# uController_and_communication.net
KiCad netlist of a schematic drawn in Altium Designer
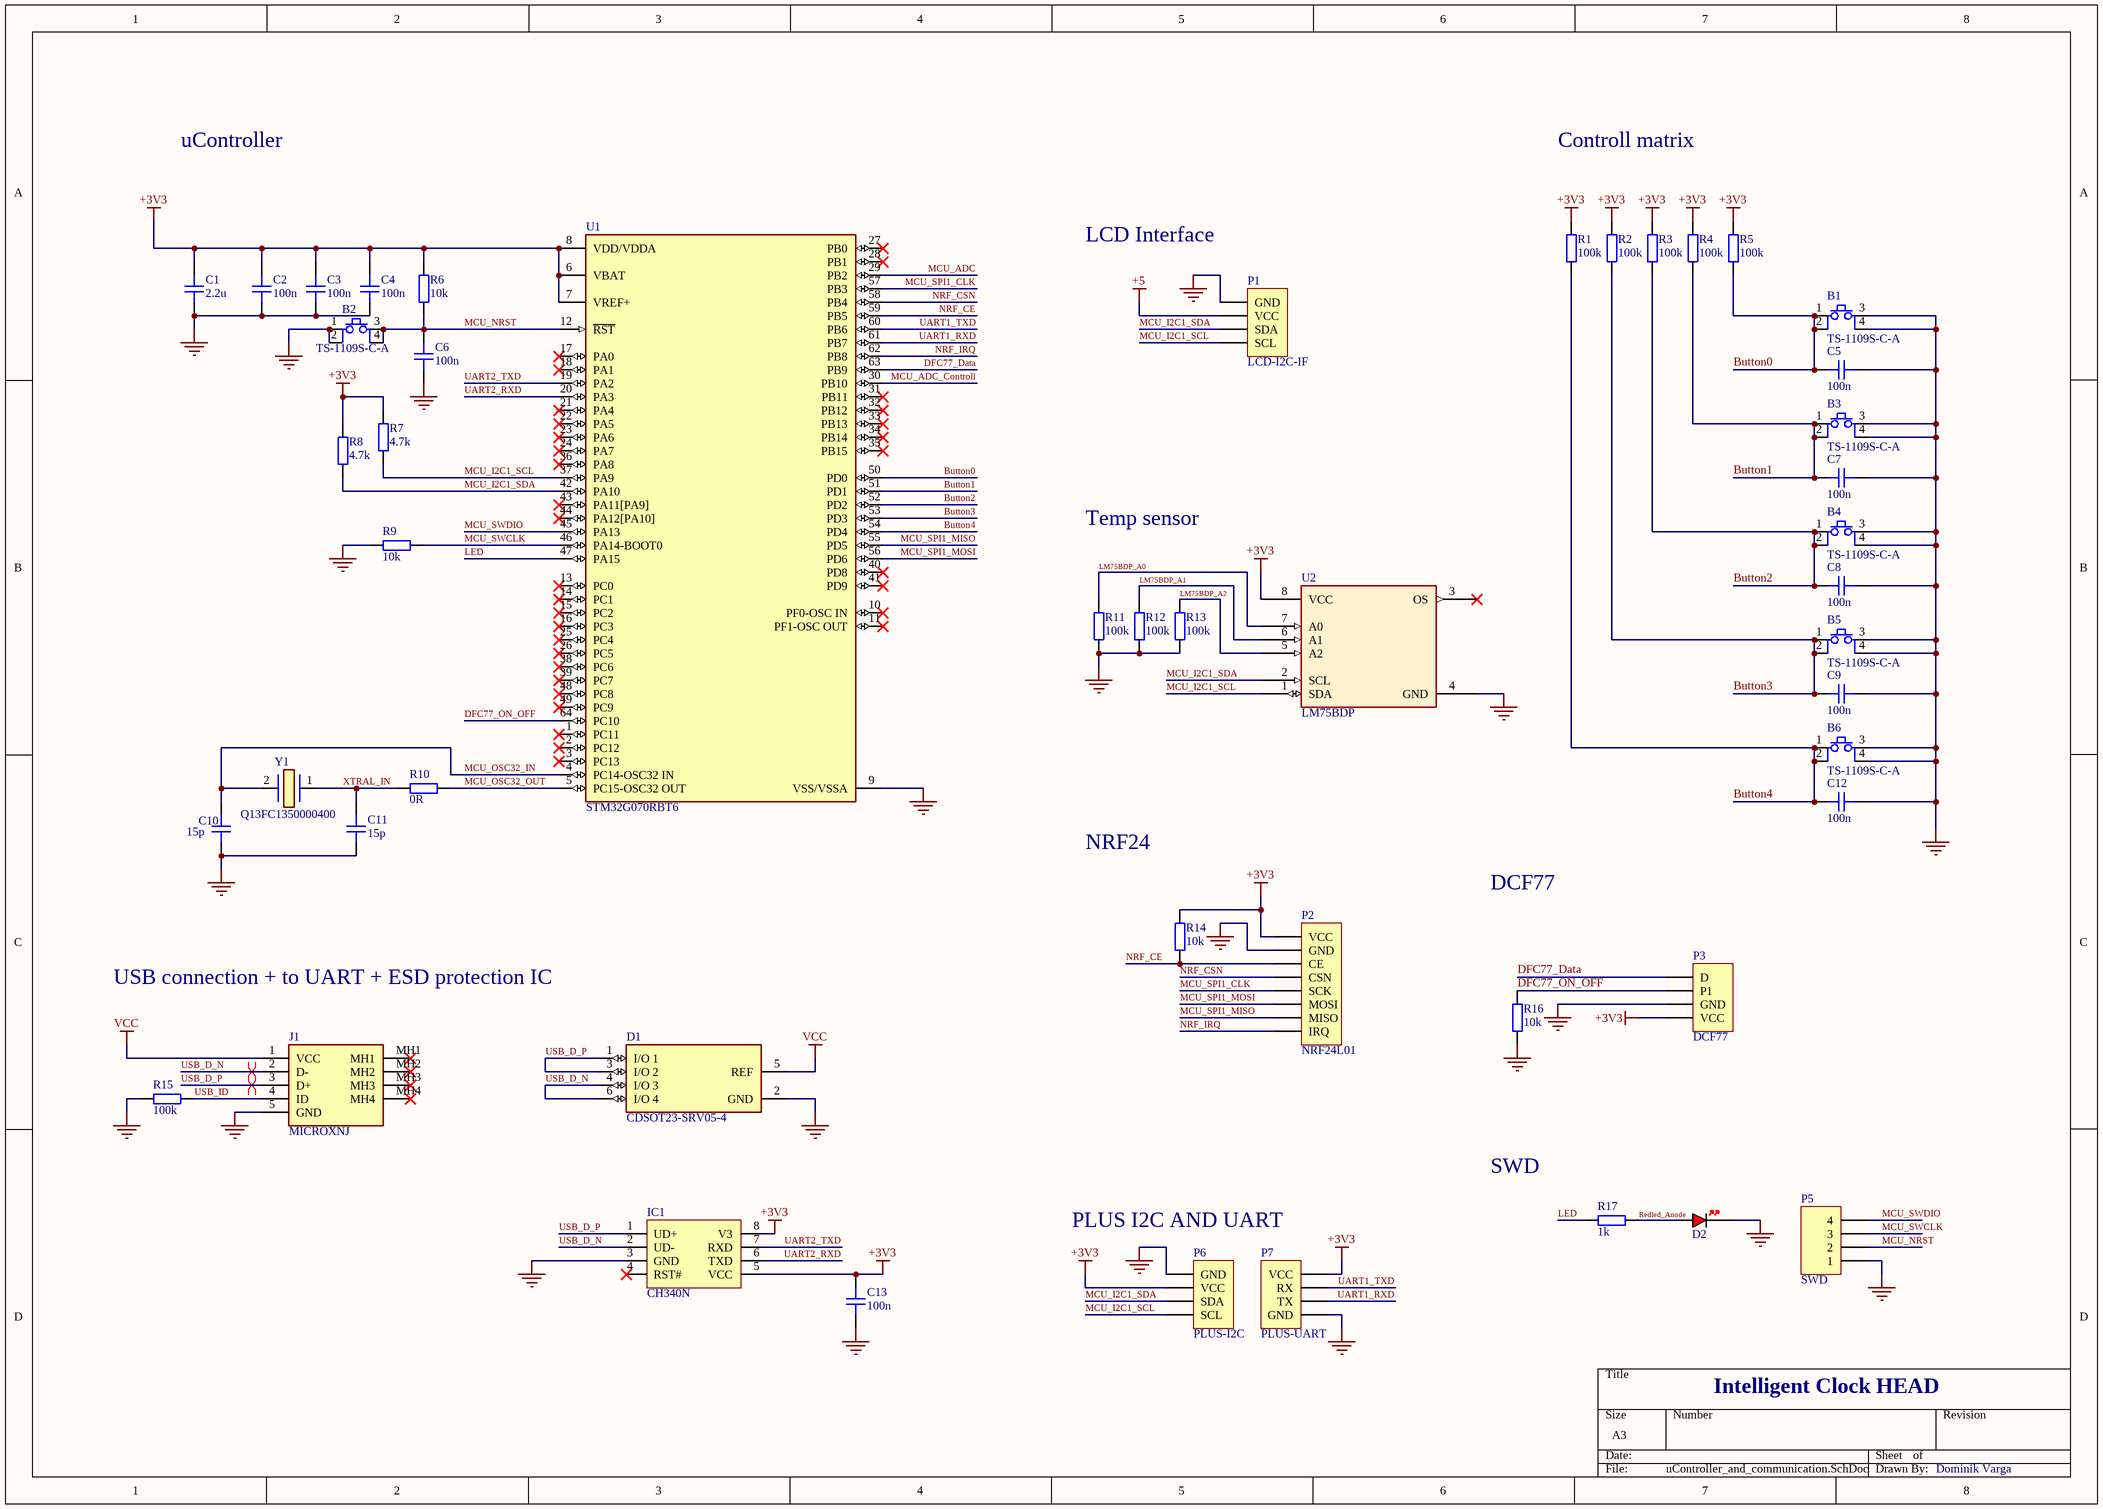
[diagram p0: uController_and_communication.SchDoc]

(export (version "E")
  (design (tool "Eeschema 10.0.6"))
  (components
    (comp (ref "B1")
      (value "TS-1109S-C-A")
      (footprint "SMD_Button")
      (description "Basic SMD button")
      (fields (field (name "MANUFACTURER") "XKB Connectivity"))
      (libsource (lib "OnlabComponents") (part "TS-1109S-C-A"))
    )
    (comp (ref "B2")
      (value "TS-1109S-C-A")
      (footprint "SMD_Button")
      (description "Basic SMD button")
      (fields (field (name "MANUFACTURER") "XKB Connectivity"))
      (libsource (lib "OnlabComponents") (part "TS-1109S-C-A"))
    )
    (comp (ref "B3")
      (value "TS-1109S-C-A")
      (footprint "SMD_Button")
      (description "Basic SMD button")
      (fields (field (name "MANUFACTURER") "XKB Connectivity"))
      (libsource (lib "OnlabComponents") (part "TS-1109S-C-A"))
    )
    (comp (ref "B4")
      (value "TS-1109S-C-A")
      (footprint "SMD_Button")
      (description "Basic SMD button")
      (fields (field (name "MANUFACTURER") "XKB Connectivity"))
      (libsource (lib "OnlabComponents") (part "TS-1109S-C-A"))
    )
    (comp (ref "B5")
      (value "TS-1109S-C-A")
      (footprint "SMD_Button")
      (description "Basic SMD button")
      (fields (field (name "MANUFACTURER") "XKB Connectivity"))
      (libsource (lib "OnlabComponents") (part "TS-1109S-C-A"))
    )
    (comp (ref "B6")
      (value "TS-1109S-C-A")
      (footprint "SMD_Button")
      (description "Basic SMD button")
      (fields (field (name "MANUFACTURER") "XKB Connectivity"))
      (libsource (lib "OnlabComponents") (part "TS-1109S-C-A"))
    )
    (comp (ref "C1")
      (value "2.2u")
      (footprint "CAP_0603")
      (description "Capacitor SMD 0603 10V")
      (libsource (lib "Schematic-Lib-PhilsLab") (part "CAP_0603_10V"))
    )
    (comp (ref "C2")
      (value "100n")
      (footprint "CAP_0603")
      (description "Capacitor SMD 0603 10V")
      (libsource (lib "Schematic-Lib-PhilsLab") (part "CAP_0603_10V"))
    )
    (comp (ref "C3")
      (value "100n")
      (footprint "CAP_0603")
      (description "Capacitor SMD 0603 10V")
      (libsource (lib "Schematic-Lib-PhilsLab") (part "CAP_0603_10V"))
    )
    (comp (ref "C4")
      (value "100n")
      (footprint "CAP_0603")
      (description "Capacitor SMD 0603 10V")
      (libsource (lib "Schematic-Lib-PhilsLab") (part "CAP_0603_10V"))
    )
    (comp (ref "C5")
      (value "100n")
      (footprint "CAP_0603")
      (description "Capacitor SMD 0603 10V")
      (libsource (lib "Schematic-Lib-PhilsLab") (part "CAP_0603_10V"))
    )
    (comp (ref "C6")
      (value "100n")
      (footprint "CAP_0603")
      (description "Capacitor SMD 0603 10V")
      (libsource (lib "Schematic-Lib-PhilsLab") (part "CAP_0603_10V"))
    )
    (comp (ref "C7")
      (value "100n")
      (footprint "CAP_0603")
      (description "Capacitor SMD 0603 10V")
      (libsource (lib "Schematic-Lib-PhilsLab") (part "CAP_0603_10V"))
    )
    (comp (ref "C8")
      (value "100n")
      (footprint "CAP_0603")
      (description "Capacitor SMD 0603 10V")
      (libsource (lib "Schematic-Lib-PhilsLab") (part "CAP_0603_10V"))
    )
    (comp (ref "C9")
      (value "100n")
      (footprint "CAP_0603")
      (description "Capacitor SMD 0603 10V")
      (libsource (lib "Schematic-Lib-PhilsLab") (part "CAP_0603_10V"))
    )
    (comp (ref "C10")
      (value "15p")
      (footprint "CAP_0603")
      (description "Capacitor SMD 0603 10V")
      (libsource (lib "Schematic-Lib-PhilsLab") (part "CAP_0603_10V"))
    )
    (comp (ref "C11")
      (value "15p")
      (footprint "CAP_0603")
      (description "Capacitor SMD 0603 10V")
      (libsource (lib "Schematic-Lib-PhilsLab") (part "CAP_0603_10V"))
    )
    (comp (ref "C12")
      (value "100n")
      (footprint "CAP_0603")
      (description "Capacitor SMD 0603 10V")
      (libsource (lib "Schematic-Lib-PhilsLab") (part "CAP_0603_10V"))
    )
    (comp (ref "C13")
      (value "100n")
      (footprint "CAP_0603")
      (description "Capacitor SMD 0603 10V")
      (libsource (lib "Schematic-Lib-PhilsLab") (part "CAP_0603_10V"))
    )
    (comp (ref "D1")
      (value "CDSOT23-SRV05-4")
      (footprint "FP-CDSOT23-SRV05-4-MFG")
      (description "TVS DIODE 5V 15V SOT23-6")
      (fields
        (field (name "OCTOPART") "https://octopart.com/cdsot23-srv05-4-bourns-1679449")
        (field (name "MANUFACTURER") "Bourns Inc.")
      )
      (libsource (lib "Altium Content Vault") (part "1f9d70c8dcd49be0b2fcd6c5f1da486"))
    )
    (comp (ref "D2")
      (value "RED")
      (footprint "LED_0603_RED")
      (description "LED 0603 RED SMD")
      (libsource (lib "Schematic-Lib-PhilsLab") (part "LED_0603_RED"))
    )
    (comp (ref "IC1")
      (value "CH340N")
      (footprint "SOP127P600X190-8N")
      (description "USB to UART integrated circuit")
      (fields (field (name "MANUFACTURER") "WCH"))
      (libsource (lib "OnlabComponents") (part "CH340N"))
    )
    (comp (ref "J1")
      (value "MICROXNJ")
      (footprint "MICROXNJ")
      (description "Connector")
      (libsource (lib "OnlabComponents") (part "MICROXNJ"))
    )
    (comp (ref "P1")
      (value "LCD-I2C-IF")
      (footprint "HDR1X4")
      (description "Header, 4-Pin")
      (fields (field (name "PUBLISHER") "Altium Limited"))
      (libsource (lib "Miscellaneous Connectors") (part "Header 4"))
    )
    (comp (ref "P2")
      (value "NRF24L01")
      (footprint "MHDR1X8")
      (description "Header, 8-Pin")
      (fields (field (name "PUBLISHER") "Altium Limited"))
      (libsource (lib "Miscellaneous Connectors") (part "MHDR1X8"))
    )
    (comp (ref "P3")
      (value "DCF77")
      (footprint "HDR1X4")
      (description "Header, 4-Pin")
      (fields (field (name "PUBLISHER") "Altium Limited"))
      (libsource (lib "Miscellaneous Connectors") (part "Header 4"))
    )
    (comp (ref "P5")
      (value "SWD")
      (footprint "HDR1X4")
      (description "Header, 4-Pin")
      (fields (field (name "PUBLISHER") "Altium Limited"))
      (libsource (lib "") (part "Header 4_1"))
    )
    (comp (ref "P6")
      (value "PLUS-I2C")
      (footprint "HDR1X4")
      (description "Header, 4-Pin")
      (fields (field (name "PUBLISHER") "Altium Limited"))
      (libsource (lib "Miscellaneous Connectors") (part "Header 4"))
    )
    (comp (ref "P7")
      (value "PLUS-UART")
      (footprint "HDR1X4")
      (description "Header, 4-Pin")
      (fields (field (name "PUBLISHER") "Altium Limited"))
      (libsource (lib "") (part "Header 4_2"))
    )
    (comp (ref "R1")
      (value "100k")
      (footprint "RES_0603")
      (description "Resistor SMD 0603")
      (libsource (lib "Schematic-Lib-PhilsLab") (part "RES_0603"))
    )
    (comp (ref "R2")
      (value "100k")
      (footprint "RES_0603")
      (description "Resistor SMD 0603")
      (libsource (lib "Schematic-Lib-PhilsLab") (part "RES_0603"))
    )
    (comp (ref "R3")
      (value "100k")
      (footprint "RES_0603")
      (description "Resistor SMD 0603")
      (libsource (lib "Schematic-Lib-PhilsLab") (part "RES_0603"))
    )
    (comp (ref "R4")
      (value "100k")
      (footprint "RES_0603")
      (description "Resistor SMD 0603")
      (libsource (lib "Schematic-Lib-PhilsLab") (part "RES_0603"))
    )
    (comp (ref "R5")
      (value "100k")
      (footprint "RES_0603")
      (description "Resistor SMD 0603")
      (libsource (lib "Schematic-Lib-PhilsLab") (part "RES_0603"))
    )
    (comp (ref "R6")
      (value "10k")
      (footprint "RES_0603")
      (description "Resistor SMD 0603")
      (libsource (lib "Schematic-Lib-PhilsLab") (part "RES_0603"))
    )
    (comp (ref "R7")
      (value "4.7k")
      (footprint "RES_0603")
      (description "Resistor SMD 0603")
      (libsource (lib "Schematic-Lib-PhilsLab") (part "RES_0603"))
    )
    (comp (ref "R8")
      (value "4.7k")
      (footprint "RES_0603")
      (description "Resistor SMD 0603")
      (libsource (lib "Schematic-Lib-PhilsLab") (part "RES_0603"))
    )
    (comp (ref "R9")
      (value "10k")
      (footprint "RES_0603")
      (description "Resistor SMD 0603")
      (libsource (lib "Schematic-Lib-PhilsLab") (part "RES_0603"))
    )
    (comp (ref "R10")
      (value "0R")
      (footprint "RES_0603")
      (description "Resistor SMD 0603")
      (libsource (lib "Schematic-Lib-PhilsLab") (part "RES_0603"))
    )
    (comp (ref "R11")
      (value "100k")
      (footprint "RES_0603")
      (description "Resistor SMD 0603")
      (libsource (lib "Schematic-Lib-PhilsLab") (part "RES_0603"))
    )
    (comp (ref "R12")
      (value "100k")
      (footprint "RES_0603")
      (description "Resistor SMD 0603")
      (libsource (lib "Schematic-Lib-PhilsLab") (part "RES_0603"))
    )
    (comp (ref "R13")
      (value "100k")
      (footprint "RES_0603")
      (description "Resistor SMD 0603")
      (libsource (lib "Schematic-Lib-PhilsLab") (part "RES_0603"))
    )
    (comp (ref "R14")
      (value "10k")
      (footprint "RES_0603")
      (description "Resistor SMD 0603")
      (libsource (lib "Schematic-Lib-PhilsLab") (part "RES_0603"))
    )
    (comp (ref "R15")
      (value "100k")
      (footprint "RES_0603")
      (description "Resistor SMD 0603")
      (libsource (lib "Schematic-Lib-PhilsLab") (part "RES_0603"))
    )
    (comp (ref "R16")
      (value "10k")
      (footprint "RES_0603")
      (description "Resistor SMD 0603")
      (libsource (lib "Schematic-Lib-PhilsLab") (part "RES_0603"))
    )
    (comp (ref "R17")
      (value "1k")
      (footprint "RES_0603")
      (description "Resistor SMD 0603")
      (libsource (lib "Schematic-Lib-PhilsLab") (part "RES_0603"))
    )
    (comp (ref "U1")
      (value "STM32G070RBT6")
      (footprint "FP-LQFP64-5W-MFG")
      (description "IC MCU 32BIT 128KB FLASH 64LQFP")
      (libsource (lib "Altium Content Vault") (part "a2e03f705dc436ee8296d2452b1f2ed"))
    )
    (comp (ref "U2")
      (value "LM75BDP")
      (footprint "TSSOP8_3P1X3P1_NXP-M")
      (description "No Description Available")
      (fields (field (name "COPYRIGHT") "Copyright (C) 2022 Ultra Librarian. All rights reserved."))
      (libsource (lib "OnlabComponents") (part "LM75BDP"))
    )
    (comp (ref "Y1")
      (value "Q13FC1350000400")
      (footprint "Q13FC1350000400")
      (description "Crystal or Oscillator")
      (libsource (lib "OnlabComponents") (part "Q13FC1350000400"))
    )
  )
  (nets
    (net (code "1") (name "+3V3") (class "Default")
      (node (ref "C1") (pin "2") (pinfunction "2_2") (pintype "passive"))
      (node (ref "C13") (pin "2") (pinfunction "2_2") (pintype "passive"))
      (node (ref "C2") (pin "2") (pinfunction "2_2") (pintype "passive"))
      (node (ref "C3") (pin "2") (pinfunction "2_2") (pintype "passive"))
      (node (ref "C4") (pin "2") (pinfunction "2_2") (pintype "passive"))
      (node (ref "IC1") (pin "5") (pinfunction "VCC_5") (pintype "passive"))
      (node (ref "IC1") (pin "8") (pinfunction "V3_8") (pintype "passive"))
      (node (ref "P2") (pin "1") (pinfunction "VCC_1") (pintype "passive"))
      (node (ref "P3") (pin "4") (pinfunction "SCL_4") (pintype "passive"))
      (node (ref "P6") (pin "2") (pinfunction "VCC_2") (pintype "passive"))
      (node (ref "P7") (pin "4") (pinfunction "VCC_4") (pintype "passive"))
      (node (ref "R1") (pin "2") (pinfunction "2_2") (pintype "passive"))
      (node (ref "R14") (pin "1") (pinfunction "1_1") (pintype "passive"))
      (node (ref "R2") (pin "2") (pinfunction "2_2") (pintype "passive"))
      (node (ref "R3") (pin "2") (pinfunction "2_2") (pintype "passive"))
      (node (ref "R4") (pin "2") (pinfunction "2_2") (pintype "passive"))
      (node (ref "R5") (pin "2") (pinfunction "2_2") (pintype "passive"))
      (node (ref "R6") (pin "2") (pinfunction "2_2") (pintype "passive"))
      (node (ref "R7") (pin "1") (pinfunction "1_1") (pintype "passive"))
      (node (ref "R8") (pin "1") (pinfunction "1_1") (pintype "passive"))
      (node (ref "U1") (pin "6") (pinfunction "VBAT_6") (pintype "power_in"))
      (node (ref "U1") (pin "7") (pinfunction "VREF+_7") (pintype "passive"))
      (node (ref "U1") (pin "8") (pinfunction "VDD/VDDA_8") (pintype "power_in"))
      (node (ref "U2") (pin "8") (pinfunction "VCC_8") (pintype "power_in"))
    )
    (net (code "2") (name "+5") (class "Default")
      (node (ref "P1") (pin "2") (pinfunction "VCC_2") (pintype "passive"))
    )
    (net (code "3") (name "/Button0") (class "Default")
      (node (ref "B1") (pin "1") (pinfunction "1_1") (pintype "passive"))
      (node (ref "B1") (pin "2") (pinfunction "2_2") (pintype "passive"))
      (node (ref "C5") (pin "1") (pinfunction "1_1") (pintype "passive"))
      (node (ref "R5") (pin "1") (pinfunction "1_1") (pintype "passive"))
      (node (ref "U1") (pin "50") (pinfunction "PD0_50") (pintype "bidirectional"))
    )
    (net (code "4") (name "/Button1") (class "Default")
      (node (ref "B3") (pin "1") (pinfunction "1_1") (pintype "passive"))
      (node (ref "B3") (pin "2") (pinfunction "2_2") (pintype "passive"))
      (node (ref "C7") (pin "1") (pinfunction "1_1") (pintype "passive"))
      (node (ref "R4") (pin "1") (pinfunction "1_1") (pintype "passive"))
      (node (ref "U1") (pin "51") (pinfunction "PD1_51") (pintype "bidirectional"))
    )
    (net (code "5") (name "/Button2") (class "Default")
      (node (ref "B4") (pin "1") (pinfunction "1_1") (pintype "passive"))
      (node (ref "B4") (pin "2") (pinfunction "2_2") (pintype "passive"))
      (node (ref "C8") (pin "1") (pinfunction "1_1") (pintype "passive"))
      (node (ref "R3") (pin "1") (pinfunction "1_1") (pintype "passive"))
      (node (ref "U1") (pin "52") (pinfunction "PD2_52") (pintype "bidirectional"))
    )
    (net (code "6") (name "/Button3") (class "Default")
      (node (ref "B5") (pin "1") (pinfunction "1_1") (pintype "passive"))
      (node (ref "B5") (pin "2") (pinfunction "2_2") (pintype "passive"))
      (node (ref "C9") (pin "1") (pinfunction "1_1") (pintype "passive"))
      (node (ref "R2") (pin "1") (pinfunction "1_1") (pintype "passive"))
      (node (ref "U1") (pin "53") (pinfunction "PD3_53") (pintype "bidirectional"))
    )
    (net (code "7") (name "/Button4") (class "Default")
      (node (ref "B6") (pin "1") (pinfunction "1_1") (pintype "passive"))
      (node (ref "B6") (pin "2") (pinfunction "2_2") (pintype "passive"))
      (node (ref "C12") (pin "1") (pinfunction "1_1") (pintype "passive"))
      (node (ref "R1") (pin "1") (pinfunction "1_1") (pintype "passive"))
      (node (ref "U1") (pin "54") (pinfunction "PD4_54") (pintype "bidirectional"))
    )
    (net (code "8") (name "/DFC77_Data") (class "Default")
      (node (ref "P3") (pin "1") (pinfunction "GND_1") (pintype "passive"))
      (node (ref "U1") (pin "63") (pinfunction "PB9_63") (pintype "bidirectional"))
    )
    (net (code "9") (name "/DFC77_ON_OFF") (class "Default")
      (node (ref "P3") (pin "2") (pinfunction "VCC_2") (pintype "passive"))
      (node (ref "R16") (pin "1") (pinfunction "1_1") (pintype "passive"))
      (node (ref "U1") (pin "64") (pinfunction "PC10_64") (pintype "bidirectional"))
    )
    (net (code "10") (name "/LED") (class "Default")
      (node (ref "R17") (pin "2") (pinfunction "2_2") (pintype "passive"))
      (node (ref "U1") (pin "47") (pinfunction "PA15_47") (pintype "bidirectional"))
    )
    (net (code "11") (name "/LM75BDP_A0") (class "Default")
      (node (ref "R11") (pin "1") (pinfunction "1_1") (pintype "passive"))
      (node (ref "U2") (pin "7") (pinfunction "A0_7") (pintype "input"))
    )
    (net (code "12") (name "/LM75BDP_A1") (class "Default")
      (node (ref "R12") (pin "1") (pinfunction "1_1") (pintype "passive"))
      (node (ref "U2") (pin "6") (pinfunction "A1_6") (pintype "input"))
    )
    (net (code "13") (name "/LM75BDP_A2") (class "Default")
      (node (ref "R13") (pin "1") (pinfunction "1_1") (pintype "passive"))
      (node (ref "U2") (pin "5") (pinfunction "A2_5") (pintype "input"))
    )
    (net (code "14") (name "/MCU_ADC") (class "Default")
      (node (ref "U1") (pin "29") (pinfunction "PB2_29") (pintype "bidirectional"))
    )
    (net (code "15") (name "/MCU_ADC_Controll") (class "Default")
      (node (ref "U1") (pin "30") (pinfunction "PB10_30") (pintype "bidirectional"))
    )
    (net (code "16") (name "/MCU_I2C1_SCL") (class "Default")
      (node (ref "P1") (pin "4") (pinfunction "SCL_4") (pintype "passive"))
      (node (ref "P6") (pin "4") (pinfunction "SCL_4") (pintype "passive"))
      (node (ref "R7") (pin "2") (pinfunction "2_2") (pintype "passive"))
      (node (ref "U1") (pin "37") (pinfunction "PA9_37") (pintype "bidirectional"))
      (node (ref "U2") (pin "1") (pinfunction "SDA_1") (pintype "bidirectional"))
    )
    (net (code "17") (name "/MCU_I2C1_SDA") (class "Default")
      (node (ref "P1") (pin "3") (pinfunction "SDA_3") (pintype "passive"))
      (node (ref "P6") (pin "3") (pinfunction "SDA_3") (pintype "passive"))
      (node (ref "R8") (pin "2") (pinfunction "2_2") (pintype "passive"))
      (node (ref "U1") (pin "42") (pinfunction "PA10_42") (pintype "bidirectional"))
      (node (ref "U2") (pin "2") (pinfunction "SCL_2") (pintype "input"))
    )
    (net (code "18") (name "/MCU_NRST") (class "Default")
      (node (ref "B2") (pin "3") (pinfunction "3_3") (pintype "passive"))
      (node (ref "B2") (pin "4") (pinfunction "4_4") (pintype "passive"))
      (node (ref "C6") (pin "2") (pinfunction "2_2") (pintype "passive"))
      (node (ref "P5") (pin "2") (pinfunction "2_2") (pintype "passive"))
      (node (ref "R6") (pin "1") (pinfunction "1_1") (pintype "passive"))
      (node (ref "U1") (pin "12") (pinfunction "~{RST}_12") (pintype "input"))
    )
    (net (code "19") (name "/MCU_OSC32_IN") (class "Default")
      (node (ref "C10") (pin "2") (pinfunction "2_2") (pintype "passive"))
      (node (ref "U1") (pin "4") (pinfunction "PC14-OSC32_IN_4") (pintype "bidirectional"))
      (node (ref "Y1") (pin "2") (pinfunction "CRYSTAL_2_2") (pintype "passive"))
    )
    (net (code "20") (name "/MCU_OSC32_OUT") (class "Default")
      (node (ref "R10") (pin "1") (pinfunction "1_1") (pintype "passive"))
      (node (ref "U1") (pin "5") (pinfunction "PC15-OSC32_OUT_5") (pintype "bidirectional"))
    )
    (net (code "21") (name "/MCU_SPI1_CLK") (class "Default")
      (node (ref "P2") (pin "5") (pinfunction "SCK_5") (pintype "passive"))
      (node (ref "U1") (pin "57") (pinfunction "PB3_57") (pintype "bidirectional"))
    )
    (net (code "22") (name "/MCU_SPI1_MISO") (class "Default")
      (node (ref "P2") (pin "7") (pinfunction "MISO_7") (pintype "passive"))
      (node (ref "U1") (pin "55") (pinfunction "PD5_55") (pintype "bidirectional"))
    )
    (net (code "23") (name "/MCU_SPI1_MOSI") (class "Default")
      (node (ref "P2") (pin "6") (pinfunction "MOSI_6") (pintype "passive"))
      (node (ref "U1") (pin "56") (pinfunction "PD6_56") (pintype "bidirectional"))
    )
    (net (code "24") (name "/MCU_SWCLK") (class "Default")
      (node (ref "P5") (pin "3") (pinfunction "3_3") (pintype "passive"))
      (node (ref "R9") (pin "1") (pinfunction "1_1") (pintype "passive"))
      (node (ref "U1") (pin "46") (pinfunction "PA14-BOOT0_46") (pintype "bidirectional"))
    )
    (net (code "25") (name "/MCU_SWDIO") (class "Default")
      (node (ref "P5") (pin "4") (pinfunction "4_4") (pintype "passive"))
      (node (ref "U1") (pin "45") (pinfunction "PA13_45") (pintype "bidirectional"))
    )
    (net (code "26") (name "/NRF_CE") (class "Default")
      (node (ref "P2") (pin "3") (pinfunction "CE_3") (pintype "passive"))
      (node (ref "R14") (pin "2") (pinfunction "2_2") (pintype "passive"))
      (node (ref "U1") (pin "59") (pinfunction "PB5_59") (pintype "bidirectional"))
    )
    (net (code "27") (name "/NRF_CSN") (class "Default")
      (node (ref "P2") (pin "4") (pinfunction "CSN_4") (pintype "passive"))
      (node (ref "U1") (pin "58") (pinfunction "PB4_58") (pintype "bidirectional"))
    )
    (net (code "28") (name "/NRF_IRQ") (class "Default")
      (node (ref "P2") (pin "8") (pinfunction "IRQ_8") (pintype "passive"))
      (node (ref "U1") (pin "62") (pinfunction "PB8_62") (pintype "bidirectional"))
    )
    (net (code "29") (name "/Redled_Anode") (class "Default")
      (node (ref "D2") (pin "A") (pinfunction "A_A") (pintype "passive"))
      (node (ref "R17") (pin "1") (pinfunction "1_1") (pintype "passive"))
    )
    (net (code "30") (name "/UART1_RXD") (class "Default")
      (node (ref "P7") (pin "2") (pinfunction "TX_2") (pintype "passive"))
      (node (ref "U1") (pin "61") (pinfunction "PB7_61") (pintype "bidirectional"))
    )
    (net (code "31") (name "/UART1_TXD") (class "Default")
      (node (ref "P7") (pin "3") (pinfunction "RX_3") (pintype "passive"))
      (node (ref "U1") (pin "60") (pinfunction "PB6_60") (pintype "bidirectional"))
    )
    (net (code "32") (name "/UART2_RXD") (class "Default")
      (node (ref "IC1") (pin "6") (pinfunction "TXD_6") (pintype "passive"))
      (node (ref "U1") (pin "20") (pinfunction "PA3_20") (pintype "bidirectional"))
    )
    (net (code "33") (name "/UART2_TXD") (class "Default")
      (node (ref "IC1") (pin "7") (pinfunction "RXD_7") (pintype "passive"))
      (node (ref "U1") (pin "19") (pinfunction "PA2_19") (pintype "bidirectional"))
    )
    (net (code "34") (name "/USB_D_N") (class "Default")
      (node (ref "D1") (pin "4") (pinfunction "I/O_3_4") (pintype "bidirectional"))
      (node (ref "D1") (pin "6") (pinfunction "I/O_4_6") (pintype "bidirectional"))
      (node (ref "IC1") (pin "2") (pinfunction "UD-_2") (pintype "passive"))
      (node (ref "J1") (pin "2") (pinfunction "D-_2") (pintype "passive"))
    )
    (net (code "35") (name "/USB_D_P") (class "Default")
      (node (ref "D1") (pin "1") (pinfunction "I/O_1_1") (pintype "bidirectional"))
      (node (ref "D1") (pin "3") (pinfunction "I/O_2_3") (pintype "bidirectional"))
      (node (ref "IC1") (pin "1") (pinfunction "UD+_1") (pintype "passive"))
      (node (ref "J1") (pin "3") (pinfunction "D+_3") (pintype "passive"))
    )
    (net (code "36") (name "/USB_ID") (class "Default")
      (node (ref "J1") (pin "4") (pinfunction "ID_4") (pintype "passive"))
      (node (ref "R15") (pin "1") (pinfunction "1_1") (pintype "passive"))
    )
    (net (code "37") (name "/XTRAL_IN") (class "Default")
      (node (ref "C11") (pin "2") (pinfunction "2_2") (pintype "passive"))
      (node (ref "R10") (pin "2") (pinfunction "2_2") (pintype "passive"))
      (node (ref "Y1") (pin "1") (pintype "passive"))
    )
    (net (code "38") (name "GND") (class "Default")
      (node (ref "B1") (pin "3") (pinfunction "3_3") (pintype "passive"))
      (node (ref "B1") (pin "4") (pinfunction "4_4") (pintype "passive"))
      (node (ref "B2") (pin "1") (pinfunction "1_1") (pintype "passive"))
      (node (ref "B2") (pin "2") (pinfunction "2_2") (pintype "passive"))
      (node (ref "B3") (pin "3") (pinfunction "3_3") (pintype "passive"))
      (node (ref "B3") (pin "4") (pinfunction "4_4") (pintype "passive"))
      (node (ref "B4") (pin "3") (pinfunction "3_3") (pintype "passive"))
      (node (ref "B4") (pin "4") (pinfunction "4_4") (pintype "passive"))
      (node (ref "B5") (pin "3") (pinfunction "3_3") (pintype "passive"))
      (node (ref "B5") (pin "4") (pinfunction "4_4") (pintype "passive"))
      (node (ref "B6") (pin "3") (pinfunction "3_3") (pintype "passive"))
      (node (ref "B6") (pin "4") (pinfunction "4_4") (pintype "passive"))
      (node (ref "C1") (pin "1") (pinfunction "1_1") (pintype "passive"))
      (node (ref "C10") (pin "1") (pinfunction "1_1") (pintype "passive"))
      (node (ref "C11") (pin "1") (pinfunction "1_1") (pintype "passive"))
      (node (ref "C12") (pin "2") (pinfunction "2_2") (pintype "passive"))
      (node (ref "C13") (pin "1") (pinfunction "1_1") (pintype "passive"))
      (node (ref "C2") (pin "1") (pinfunction "1_1") (pintype "passive"))
      (node (ref "C3") (pin "1") (pinfunction "1_1") (pintype "passive"))
      (node (ref "C4") (pin "1") (pinfunction "1_1") (pintype "passive"))
      (node (ref "C5") (pin "2") (pinfunction "2_2") (pintype "passive"))
      (node (ref "C6") (pin "1") (pinfunction "1_1") (pintype "passive"))
      (node (ref "C7") (pin "2") (pinfunction "2_2") (pintype "passive"))
      (node (ref "C8") (pin "2") (pinfunction "2_2") (pintype "passive"))
      (node (ref "C9") (pin "2") (pinfunction "2_2") (pintype "passive"))
      (node (ref "D1") (pin "2") (pinfunction "GND_2") (pintype "power_in"))
      (node (ref "D2") (pin "K") (pinfunction "K_K") (pintype "passive"))
      (node (ref "IC1") (pin "3") (pinfunction "GND_3") (pintype "passive"))
      (node (ref "J1") (pin "5") (pinfunction "GND_5") (pintype "passive"))
      (node (ref "P1") (pin "1") (pinfunction "GND_1") (pintype "passive"))
      (node (ref "P2") (pin "2") (pinfunction "GND_2") (pintype "passive"))
      (node (ref "P3") (pin "3") (pinfunction "SDA_3") (pintype "passive"))
      (node (ref "P5") (pin "1") (pinfunction "1_1") (pintype "passive"))
      (node (ref "P6") (pin "1") (pinfunction "GND_1") (pintype "passive"))
      (node (ref "P7") (pin "1") (pinfunction "GND_1") (pintype "passive"))
      (node (ref "R11") (pin "2") (pinfunction "2_2") (pintype "passive"))
      (node (ref "R12") (pin "2") (pinfunction "2_2") (pintype "passive"))
      (node (ref "R13") (pin "2") (pinfunction "2_2") (pintype "passive"))
      (node (ref "R15") (pin "2") (pinfunction "2_2") (pintype "passive"))
      (node (ref "R16") (pin "2") (pinfunction "2_2") (pintype "passive"))
      (node (ref "R9") (pin "2") (pinfunction "2_2") (pintype "passive"))
      (node (ref "U1") (pin "9") (pinfunction "VSS/VSSA_9") (pintype "power_in"))
      (node (ref "U2") (pin "4") (pinfunction "GND_4") (pintype "power_in"))
    )
    (net (code "39") (name "VCC") (class "Default")
      (node (ref "D1") (pin "5") (pinfunction "REF_5") (pintype "power_in"))
      (node (ref "J1") (pin "1") (pinfunction "VCC_1") (pintype "passive"))
    )
    (net (code "40") (name "unconnected-(IC1-RST#-Pad4)") (class "Default")
      (node (ref "IC1") (pin "4") (pinfunction "RST#_4") (pintype "passive+no_connect"))
    )
    (net (code "41") (name "unconnected-(J1-PadMH1)") (class "Default")
      (node (ref "J1") (pin "MH1") (pinfunction "MH1_MH1") (pintype "passive+no_connect"))
    )
    (net (code "42") (name "unconnected-(J1-PadMH2)") (class "Default")
      (node (ref "J1") (pin "MH2") (pinfunction "MH2_MH2") (pintype "passive+no_connect"))
    )
    (net (code "43") (name "unconnected-(J1-PadMH3)") (class "Default")
      (node (ref "J1") (pin "MH3") (pinfunction "MH3_MH3") (pintype "passive+no_connect"))
    )
    (net (code "44") (name "unconnected-(J1-PadMH4)") (class "Default")
      (node (ref "J1") (pin "MH4") (pinfunction "MH4_MH4") (pintype "passive+no_connect"))
    )
    (net (code "45") (name "unconnected-(U1-PA0-Pad17)") (class "Default")
      (node (ref "U1") (pin "17") (pinfunction "PA0_17") (pintype "bidirectional+no_connect"))
    )
    (net (code "46") (name "unconnected-(U1-PA1-Pad18)") (class "Default")
      (node (ref "U1") (pin "18") (pinfunction "PA1_18") (pintype "bidirectional+no_connect"))
    )
    (net (code "47") (name "unconnected-(U1-PA4-Pad21)") (class "Default")
      (node (ref "U1") (pin "21") (pinfunction "PA4_21") (pintype "bidirectional+no_connect"))
    )
    (net (code "48") (name "unconnected-(U1-PA5-Pad22)") (class "Default")
      (node (ref "U1") (pin "22") (pinfunction "PA5_22") (pintype "bidirectional+no_connect"))
    )
    (net (code "49") (name "unconnected-(U1-PA6-Pad23)") (class "Default")
      (node (ref "U1") (pin "23") (pinfunction "PA6_23") (pintype "bidirectional+no_connect"))
    )
    (net (code "50") (name "unconnected-(U1-PA7-Pad24)") (class "Default")
      (node (ref "U1") (pin "24") (pinfunction "PA7_24") (pintype "bidirectional+no_connect"))
    )
    (net (code "51") (name "unconnected-(U1-PA8-Pad36)") (class "Default")
      (node (ref "U1") (pin "36") (pinfunction "PA8_36") (pintype "bidirectional+no_connect"))
    )
    (net (code "52") (name "unconnected-(U1-PA11[PA9]-Pad43)") (class "Default")
      (node (ref "U1") (pin "43") (pinfunction "PA11[PA9]_43") (pintype "bidirectional+no_connect"))
    )
    (net (code "53") (name "unconnected-(U1-PA12[PA10]-Pad44)") (class "Default")
      (node (ref "U1") (pin "44") (pinfunction "PA12[PA10]_44") (pintype "bidirectional+no_connect"))
    )
    (net (code "54") (name "unconnected-(U1-PB0-Pad27)") (class "Default")
      (node (ref "U1") (pin "27") (pinfunction "PB0_27") (pintype "bidirectional+no_connect"))
    )
    (net (code "55") (name "unconnected-(U1-PB1-Pad28)") (class "Default")
      (node (ref "U1") (pin "28") (pinfunction "PB1_28") (pintype "bidirectional+no_connect"))
    )
    (net (code "56") (name "unconnected-(U1-PB11-Pad31)") (class "Default")
      (node (ref "U1") (pin "31") (pinfunction "PB11_31") (pintype "bidirectional+no_connect"))
    )
    (net (code "57") (name "unconnected-(U1-PB12-Pad32)") (class "Default")
      (node (ref "U1") (pin "32") (pinfunction "PB12_32") (pintype "bidirectional+no_connect"))
    )
    (net (code "58") (name "unconnected-(U1-PB13-Pad33)") (class "Default")
      (node (ref "U1") (pin "33") (pinfunction "PB13_33") (pintype "bidirectional+no_connect"))
    )
    (net (code "59") (name "unconnected-(U1-PB14-Pad34)") (class "Default")
      (node (ref "U1") (pin "34") (pinfunction "PB14_34") (pintype "bidirectional+no_connect"))
    )
    (net (code "60") (name "unconnected-(U1-PB15-Pad35)") (class "Default")
      (node (ref "U1") (pin "35") (pinfunction "PB15_35") (pintype "bidirectional+no_connect"))
    )
    (net (code "61") (name "unconnected-(U1-PC0-Pad13)") (class "Default")
      (node (ref "U1") (pin "13") (pinfunction "PC0_13") (pintype "bidirectional+no_connect"))
    )
    (net (code "62") (name "unconnected-(U1-PC1-Pad14)") (class "Default")
      (node (ref "U1") (pin "14") (pinfunction "PC1_14") (pintype "bidirectional+no_connect"))
    )
    (net (code "63") (name "unconnected-(U1-PC2-Pad15)") (class "Default")
      (node (ref "U1") (pin "15") (pinfunction "PC2_15") (pintype "bidirectional+no_connect"))
    )
    (net (code "64") (name "unconnected-(U1-PC3-Pad16)") (class "Default")
      (node (ref "U1") (pin "16") (pinfunction "PC3_16") (pintype "bidirectional+no_connect"))
    )
    (net (code "65") (name "unconnected-(U1-PC4-Pad25)") (class "Default")
      (node (ref "U1") (pin "25") (pinfunction "PC4_25") (pintype "bidirectional+no_connect"))
    )
    (net (code "66") (name "unconnected-(U1-PC5-Pad26)") (class "Default")
      (node (ref "U1") (pin "26") (pinfunction "PC5_26") (pintype "bidirectional+no_connect"))
    )
    (net (code "67") (name "unconnected-(U1-PC6-Pad38)") (class "Default")
      (node (ref "U1") (pin "38") (pinfunction "PC6_38") (pintype "bidirectional+no_connect"))
    )
    (net (code "68") (name "unconnected-(U1-PC7-Pad39)") (class "Default")
      (node (ref "U1") (pin "39") (pinfunction "PC7_39") (pintype "bidirectional+no_connect"))
    )
    (net (code "69") (name "unconnected-(U1-PC8-Pad48)") (class "Default")
      (node (ref "U1") (pin "48") (pinfunction "PC8_48") (pintype "bidirectional+no_connect"))
    )
    (net (code "70") (name "unconnected-(U1-PC9-Pad49)") (class "Default")
      (node (ref "U1") (pin "49") (pinfunction "PC9_49") (pintype "bidirectional+no_connect"))
    )
    (net (code "71") (name "unconnected-(U1-PC11-Pad1)") (class "Default")
      (node (ref "U1") (pin "1") (pinfunction "PC11_1") (pintype "bidirectional+no_connect"))
    )
    (net (code "72") (name "unconnected-(U1-PC12-Pad2)") (class "Default")
      (node (ref "U1") (pin "2") (pinfunction "PC12_2") (pintype "bidirectional+no_connect"))
    )
    (net (code "73") (name "unconnected-(U1-PC13-Pad3)") (class "Default")
      (node (ref "U1") (pin "3") (pinfunction "PC13_3") (pintype "bidirectional+no_connect"))
    )
    (net (code "74") (name "unconnected-(U1-PD8-Pad40)") (class "Default")
      (node (ref "U1") (pin "40") (pinfunction "PD8_40") (pintype "bidirectional+no_connect"))
    )
    (net (code "75") (name "unconnected-(U1-PD9-Pad41)") (class "Default")
      (node (ref "U1") (pin "41") (pinfunction "PD9_41") (pintype "bidirectional+no_connect"))
    )
    (net (code "76") (name "unconnected-(U1-PF0-OSC_IN-Pad10)") (class "Default")
      (node (ref "U1") (pin "10") (pinfunction "PF0-OSC_IN_10") (pintype "bidirectional+no_connect"))
    )
    (net (code "77") (name "unconnected-(U1-PF1-OSC_OUT-Pad11)") (class "Default")
      (node (ref "U1") (pin "11") (pinfunction "PF1-OSC_OUT_11") (pintype "bidirectional+no_connect"))
    )
    (net (code "78") (name "unconnected-(U2-OS-Pad3)") (class "Default")
      (node (ref "U2") (pin "3") (pinfunction "OS_3") (pintype "output+no_connect"))
    )
  )
)
